# schematic.net
KiCad netlist of a schematic drawn in Altium Designer
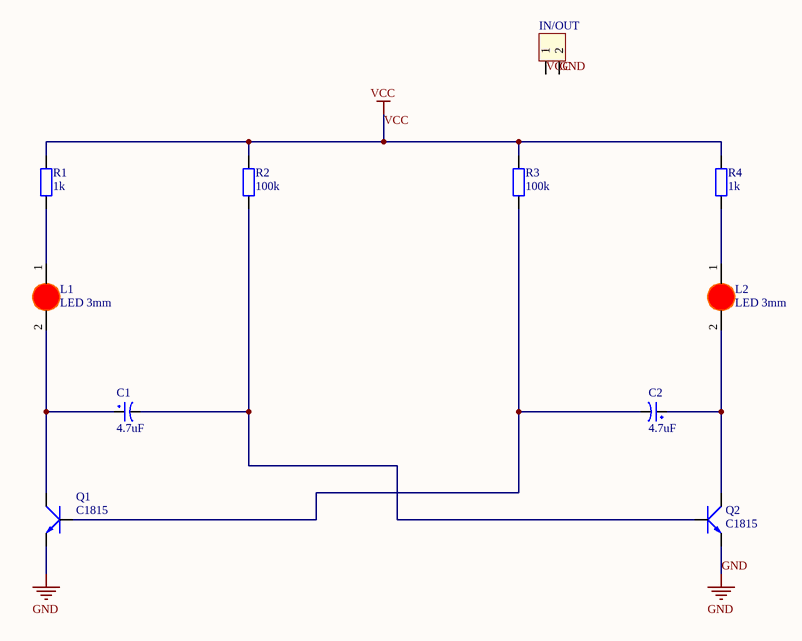
[diagram p0: schematic.SchDoc]

(export (version "E")
  (design (tool "Eeschema 10.0.6"))
  (components
    (comp (ref "C1")
      (value "4.7uF")
      (footprint "tu hoa 8mm")
      (description "Cắm")
      (libsource (lib "Capacitor") (part "Tu Hoa 4.7uF 400V 8x12"))
    )
    (comp (ref "C2")
      (value "4.7uF")
      (footprint "tu hoa 8mm")
      (description "Cắm")
      (libsource (lib "Capacitor") (part "Tu Hoa 4.7uF 400V 8x12"))
    )
    (comp (ref "IN/OUT")
      (value "Header 2")
      (footprint "HED2")
      (description "Header 2 (Green)")
      (libsource (lib "syhaunguyen") (part "Hed2"))
    )
    (comp (ref "L1")
      (value "LED 3mm")
      (footprint "LED-3MM-RED")
      (description "Cắm")
      (libsource (lib "Led") (part "LED 3mm Do"))
    )
    (comp (ref "L2")
      (value "LED 3mm")
      (footprint "LED-3MM-RED")
      (description "Cắm")
      (libsource (lib "Led") (part "LED 3mm Do"))
    )
    (comp (ref "Q1")
      (value "C1815")
      (footprint "QTO-92")
      (description "NPN 600mW, ECB")
      (libsource (lib "syhaunguyen") (part "C1815"))
    )
    (comp (ref "Q2")
      (value "C1815")
      (footprint "QTO-92")
      (description "NPN 600mW, ECB")
      (libsource (lib "syhaunguyen") (part "C1815"))
    )
    (comp (ref "R1")
      (value "1k")
      (footprint "tro vach 1/4w")
      (description "Cắm")
      (libsource (lib "Resistor") (part "Tro Vach 1/4W 5% 1k"))
    )
    (comp (ref "R2")
      (value "100k")
      (footprint "tro vach 1/4w")
      (description "Cắm")
      (libsource (lib "Resistor") (part "Tro Vach 1/4W 5% 100k"))
    )
    (comp (ref "R3")
      (value "100k")
      (footprint "tro vach 1/4w")
      (description "Cắm")
      (libsource (lib "Resistor") (part "Tro Vach 1/4W 5% 100k"))
    )
    (comp (ref "R4")
      (value "1k")
      (footprint "tro vach 1/4w")
      (description "Cắm")
      (libsource (lib "Resistor") (part "Tro Vach 1/4W 5% 1k"))
    )
  )
  (nets
    (net (code "1") (name "GND") (class "Default")
      (node (ref "IN/OUT") (pin "2") (pinfunction "2_2") (pintype "passive"))
      (node (ref "Q1") (pin "1") (pinfunction "E_1") (pintype "passive"))
      (node (ref "Q2") (pin "1") (pinfunction "E_1") (pintype "passive"))
    )
    (net (code "2") (name "Net-(L1-A)") (class "Default")
      (node (ref "L1") (pin "1") (pinfunction "A_1") (pintype "passive"))
      (node (ref "R1") (pin "1") (pinfunction "1_1") (pintype "passive"))
    )
    (net (code "3") (name "Net-(L1-K)") (class "Default")
      (node (ref "C1") (pin "1") (pinfunction "1_1") (pintype "passive"))
      (node (ref "L1") (pin "2") (pinfunction "K_2") (pintype "passive"))
      (node (ref "Q1") (pin "2") (pinfunction "C_2") (pintype "passive"))
    )
    (net (code "4") (name "Net-(L2-A)") (class "Default")
      (node (ref "L2") (pin "1") (pinfunction "A_1") (pintype "passive"))
      (node (ref "R4") (pin "1") (pinfunction "1_1") (pintype "passive"))
    )
    (net (code "5") (name "Net-(L2-K)") (class "Default")
      (node (ref "C2") (pin "1") (pinfunction "1_1") (pintype "passive"))
      (node (ref "L2") (pin "2") (pinfunction "K_2") (pintype "passive"))
      (node (ref "Q2") (pin "2") (pinfunction "C_2") (pintype "passive"))
    )
    (net (code "6") (name "Net-(Q1-B)") (class "Default")
      (node (ref "C2") (pin "2") (pinfunction "2_2") (pintype "passive"))
      (node (ref "Q1") (pin "3") (pinfunction "B_3") (pintype "passive"))
      (node (ref "R3") (pin "1") (pinfunction "1_1") (pintype "passive"))
    )
    (net (code "7") (name "Net-(Q2-B)") (class "Default")
      (node (ref "C1") (pin "2") (pinfunction "2_2") (pintype "passive"))
      (node (ref "Q2") (pin "3") (pinfunction "B_3") (pintype "passive"))
      (node (ref "R2") (pin "1") (pinfunction "1_1") (pintype "passive"))
    )
    (net (code "8") (name "VCC") (class "Default")
      (node (ref "IN/OUT") (pin "1") (pinfunction "1_1") (pintype "passive"))
      (node (ref "R1") (pin "2") (pinfunction "2_2") (pintype "passive"))
      (node (ref "R2") (pin "2") (pinfunction "2_2") (pintype "passive"))
      (node (ref "R3") (pin "2") (pinfunction "2_2") (pintype "passive"))
      (node (ref "R4") (pin "2") (pinfunction "2_2") (pintype "passive"))
    )
  )
)
